# NodeMCUtoMFRC522.net
KiCad netlist of a schematic drawn in EAGLE
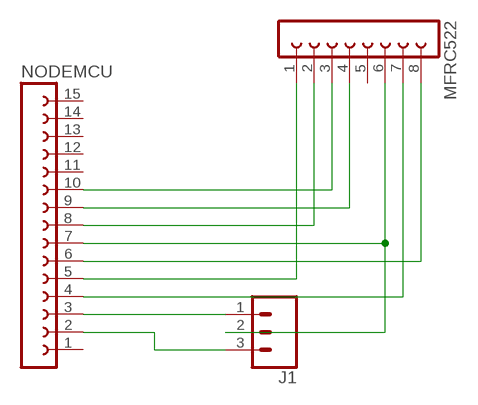
[diagram p0: schematic, sheet 1]

(export (version "E")
  (design (tool "Eeschema 10.0.6"))
  (components
    (comp (ref "J1")
      (value "CONN_03POLAR")
      (footprint "eagle-import:MOLEX-1X3")
      (libsource (lib "eagle-import") (part "CONN_03POLAR"))
    )
    (comp (ref "MFRC522")
      (value "FE08-1")
      (footprint "eagle-import:FE08")
      (libsource (lib "eagle-import") (part "FE08-1"))
    )
    (comp (ref "NODEMCU")
      (value "FE15-1")
      (footprint "eagle-import:FE15")
      (libsource (lib "eagle-import") (part "FE15-1"))
    )
  )
  (nets
    (net (code "1") (name "Net-(J1-Pad1)") (class "Default")
      (node (ref "J1") (pin "1") (pinfunction "1_1") (pintype "passive"))
      (node (ref "NODEMCU") (pin "3") (pinfunction "3_3") (pintype "passive"))
    )
    (net (code "2") (name "Net-(J1-Pad2)") (class "Default")
      (node (ref "J1") (pin "2") (pinfunction "2_2") (pintype "passive"))
      (node (ref "MFRC522") (pin "6") (pinfunction "6_6") (pintype "passive"))
      (node (ref "NODEMCU") (pin "7") (pinfunction "7_7") (pintype "passive"))
    )
    (net (code "3") (name "Net-(J1-Pad3)") (class "Default")
      (node (ref "J1") (pin "3") (pinfunction "3_3") (pintype "passive"))
      (node (ref "NODEMCU") (pin "2") (pinfunction "2_2") (pintype "passive"))
    )
    (net (code "4") (name "Net-(MFRC522-Pad1)") (class "Default")
      (node (ref "MFRC522") (pin "1") (pinfunction "1_1") (pintype "passive"))
      (node (ref "NODEMCU") (pin "5") (pinfunction "5_5") (pintype "passive"))
    )
    (net (code "5") (name "Net-(MFRC522-Pad2)") (class "Default")
      (node (ref "MFRC522") (pin "2") (pinfunction "2_2") (pintype "passive"))
      (node (ref "NODEMCU") (pin "8") (pinfunction "8_8") (pintype "passive"))
    )
    (net (code "6") (name "Net-(MFRC522-Pad3)") (class "Default")
      (node (ref "MFRC522") (pin "3") (pinfunction "3_3") (pintype "passive"))
      (node (ref "NODEMCU") (pin "10") (pinfunction "10_10") (pintype "passive"))
    )
    (net (code "7") (name "Net-(MFRC522-Pad4)") (class "Default")
      (node (ref "MFRC522") (pin "4") (pinfunction "4_4") (pintype "passive"))
      (node (ref "NODEMCU") (pin "9") (pinfunction "9_9") (pintype "passive"))
    )
    (net (code "8") (name "Net-(MFRC522-Pad7)") (class "Default")
      (node (ref "MFRC522") (pin "7") (pinfunction "7_7") (pintype "passive"))
      (node (ref "NODEMCU") (pin "4") (pinfunction "4_4") (pintype "passive"))
    )
    (net (code "9") (name "Net-(MFRC522-Pad8)") (class "Default")
      (node (ref "MFRC522") (pin "8") (pinfunction "8_8") (pintype "passive"))
      (node (ref "NODEMCU") (pin "6") (pinfunction "6_6") (pintype "passive"))
    )
    (net (code "10") (name "unconnected-(MFRC522-Pad5)") (class "Default")
      (node (ref "MFRC522") (pin "5") (pinfunction "5_5") (pintype "passive"))
    )
    (net (code "11") (name "unconnected-(NODEMCU-Pad1)") (class "Default")
      (node (ref "NODEMCU") (pin "1") (pinfunction "1_1") (pintype "passive"))
    )
    (net (code "12") (name "unconnected-(NODEMCU-Pad11)") (class "Default")
      (node (ref "NODEMCU") (pin "11") (pinfunction "11_11") (pintype "passive"))
    )
    (net (code "13") (name "unconnected-(NODEMCU-Pad12)") (class "Default")
      (node (ref "NODEMCU") (pin "12") (pinfunction "12_12") (pintype "passive"))
    )
    (net (code "14") (name "unconnected-(NODEMCU-Pad13)") (class "Default")
      (node (ref "NODEMCU") (pin "13") (pinfunction "13_13") (pintype "passive"))
    )
    (net (code "15") (name "unconnected-(NODEMCU-Pad14)") (class "Default")
      (node (ref "NODEMCU") (pin "14") (pinfunction "14_14") (pintype "passive"))
    )
    (net (code "16") (name "unconnected-(NODEMCU-Pad15)") (class "Default")
      (node (ref "NODEMCU") (pin "15") (pinfunction "15_15") (pintype "passive"))
    )
  )
)
